# MAX31855T.net
KiCad netlist of a schematic drawn in EAGLE
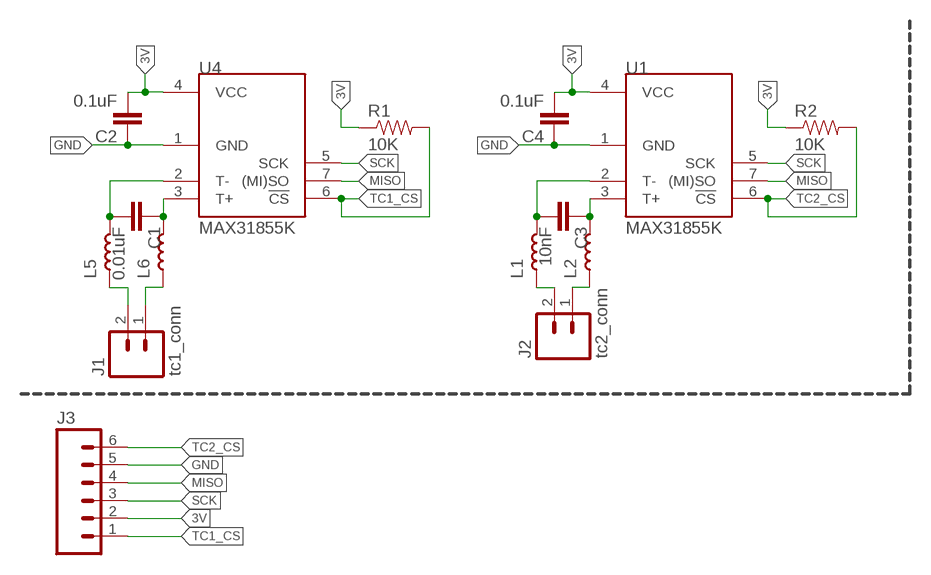
[diagram p0: schematic, sheet 1]

(export (version "E")
  (design (tool "Eeschema 10.0.6"))
  (components
    (comp (ref "C1")
      (value "0.01uF")
      (footprint "eagle-import:0603-CAP")
      (libsource (lib "eagle-import") (part "10NF/10000PF-50V-10%(0603)"))
    )
    (comp (ref "C2")
      (value "0.1uF")
      (footprint "eagle-import:0603-CAP")
      (libsource (lib "eagle-import") (part "0.1UF-25V(+80/-20%)(0603)"))
    )
    (comp (ref "C3")
      (value "10nF")
      (footprint "eagle-import:0603-CAP")
      (libsource (lib "eagle-import") (part "10NF/10000PF-50V-10%(0603)"))
    )
    (comp (ref "C4")
      (value "0.1uF")
      (footprint "eagle-import:0603-CAP")
      (libsource (lib "eagle-import") (part "0.1UF-25V(+80/-20%)(0603)"))
    )
    (comp (ref "J1")
      (value "tc1_conn")
      (footprint "eagle-import:1X02_LONGPADS")
      (libsource (lib "eagle-import") (part "M02PTH3"))
    )
    (comp (ref "J2")
      (value "tc2_conn")
      (footprint "eagle-import:1X02_LONGPADS")
      (libsource (lib "eagle-import") (part "M02PTH3"))
    )
    (comp (ref "J3")
      (value "M06LONGPADS")
      (footprint "eagle-import:1X06_LONGPADS")
      (libsource (lib "eagle-import") (part "M06LONGPADS"))
    )
    (comp (ref "L1")
      (value "INDUCTOR0603-N")
      (footprint "eagle-import:L0603-N")
      (libsource (lib "eagle-import") (part "INDUCTOR0603-N"))
    )
    (comp (ref "L2")
      (value "INDUCTOR0603-N")
      (footprint "eagle-import:L0603-N")
      (libsource (lib "eagle-import") (part "INDUCTOR0603-N"))
    )
    (comp (ref "L5")
      (value "INDUCTOR0603-N")
      (footprint "eagle-import:L0603-N")
      (libsource (lib "eagle-import") (part "INDUCTOR0603-N"))
    )
    (comp (ref "L6")
      (value "INDUCTOR0603-N")
      (footprint "eagle-import:L0603-N")
      (libsource (lib "eagle-import") (part "INDUCTOR0603-N"))
    )
    (comp (ref "R1")
      (value "10K")
      (footprint "eagle-import:0603-RES")
      (libsource (lib "eagle-import") (part "10KOHM-1/10W-1%(0603)0603"))
    )
    (comp (ref "R2")
      (value "10K")
      (footprint "eagle-import:0603-RES")
      (libsource (lib "eagle-import") (part "10KOHM-1/10W-1%(0603)0603"))
    )
    (comp (ref "U1")
      (value "MAX31855K")
      (footprint "eagle-import:SOIC8")
      (libsource (lib "eagle-import") (part "MAX31855K"))
    )
    (comp (ref "U4")
      (value "MAX31855K")
      (footprint "eagle-import:SOIC8")
      (libsource (lib "eagle-import") (part "MAX31855K"))
    )
  )
  (nets
    (net (code "1") (name "3V") (class "Default")
      (node (ref "C2") (pin "2") (pinfunction "2_2") (pintype "passive"))
      (node (ref "C4") (pin "2") (pinfunction "2_2") (pintype "passive"))
      (node (ref "J3") (pin "2") (pinfunction "2_2") (pintype "passive"))
      (node (ref "R1") (pin "1") (pinfunction "1_1") (pintype "passive"))
      (node (ref "R2") (pin "1") (pinfunction "1_1") (pintype "passive"))
      (node (ref "U1") (pin "4") (pinfunction "VCC_4") (pintype "bidirectional"))
      (node (ref "U4") (pin "4") (pinfunction "VCC_4") (pintype "bidirectional"))
    )
    (net (code "2") (name "GND") (class "Default")
      (node (ref "C2") (pin "1") (pinfunction "1_1") (pintype "passive"))
      (node (ref "C4") (pin "1") (pinfunction "1_1") (pintype "passive"))
      (node (ref "J3") (pin "5") (pinfunction "5_5") (pintype "passive"))
      (node (ref "U1") (pin "1") (pinfunction "GND_1") (pintype "bidirectional"))
      (node (ref "U4") (pin "1") (pinfunction "GND_1") (pintype "bidirectional"))
    )
    (net (code "3") (name "MISO") (class "Default")
      (node (ref "J3") (pin "4") (pinfunction "4_4") (pintype "passive"))
      (node (ref "U1") (pin "7") (pinfunction "(MI)SO_7") (pintype "bidirectional"))
      (node (ref "U4") (pin "7") (pinfunction "(MI)SO_7") (pintype "bidirectional"))
    )
    (net (code "4") (name "Net-(L1-P$1)") (class "Default")
      (node (ref "J2") (pin "2") (pinfunction "2_2") (pintype "passive"))
      (node (ref "L1") (pin "1") (pinfunction "P$1_1") (pintype "passive"))
    )
    (net (code "5") (name "Net-(L1-P$2)") (class "Default")
      (node (ref "C3") (pin "2") (pinfunction "2_2") (pintype "passive"))
      (node (ref "L1") (pin "2") (pinfunction "P$2_2") (pintype "passive"))
      (node (ref "U1") (pin "2") (pinfunction "T-_2") (pintype "bidirectional"))
    )
    (net (code "6") (name "Net-(L2-P$1)") (class "Default")
      (node (ref "J2") (pin "1") (pinfunction "1_1") (pintype "passive"))
      (node (ref "L2") (pin "1") (pinfunction "P$1_1") (pintype "passive"))
    )
    (net (code "7") (name "Net-(L2-P$2)") (class "Default")
      (node (ref "C3") (pin "1") (pinfunction "1_1") (pintype "passive"))
      (node (ref "L2") (pin "2") (pinfunction "P$2_2") (pintype "passive"))
      (node (ref "U1") (pin "3") (pinfunction "T+_3") (pintype "bidirectional"))
    )
    (net (code "8") (name "Net-(L5-P$1)") (class "Default")
      (node (ref "J1") (pin "2") (pinfunction "2_2") (pintype "passive"))
      (node (ref "L5") (pin "1") (pinfunction "P$1_1") (pintype "passive"))
    )
    (net (code "9") (name "Net-(L5-P$2)") (class "Default")
      (node (ref "C1") (pin "2") (pinfunction "2_2") (pintype "passive"))
      (node (ref "L5") (pin "2") (pinfunction "P$2_2") (pintype "passive"))
      (node (ref "U4") (pin "2") (pinfunction "T-_2") (pintype "bidirectional"))
    )
    (net (code "10") (name "Net-(L6-P$1)") (class "Default")
      (node (ref "J1") (pin "1") (pinfunction "1_1") (pintype "passive"))
      (node (ref "L6") (pin "1") (pinfunction "P$1_1") (pintype "passive"))
    )
    (net (code "11") (name "Net-(L6-P$2)") (class "Default")
      (node (ref "C1") (pin "1") (pinfunction "1_1") (pintype "passive"))
      (node (ref "L6") (pin "2") (pinfunction "P$2_2") (pintype "passive"))
      (node (ref "U4") (pin "3") (pinfunction "T+_3") (pintype "bidirectional"))
    )
    (net (code "12") (name "SCK") (class "Default")
      (node (ref "J3") (pin "3") (pinfunction "3_3") (pintype "passive"))
      (node (ref "U1") (pin "5") (pinfunction "SCK_5") (pintype "bidirectional"))
      (node (ref "U4") (pin "5") (pinfunction "SCK_5") (pintype "bidirectional"))
    )
    (net (code "13") (name "TC1_CS") (class "Default")
      (node (ref "J3") (pin "1") (pinfunction "1_1") (pintype "passive"))
      (node (ref "R1") (pin "2") (pinfunction "2_2") (pintype "passive"))
      (node (ref "U4") (pin "6") (pinfunction "~{CS}_6") (pintype "bidirectional"))
    )
    (net (code "14") (name "TC2_CS") (class "Default")
      (node (ref "J3") (pin "6") (pinfunction "6_6") (pintype "passive"))
      (node (ref "R2") (pin "2") (pinfunction "2_2") (pintype "passive"))
      (node (ref "U1") (pin "6") (pinfunction "~{CS}_6") (pintype "bidirectional"))
    )
  )
)
